# MHR15-GLV_PWR.net
KiCad netlist of a schematic drawn in EAGLE
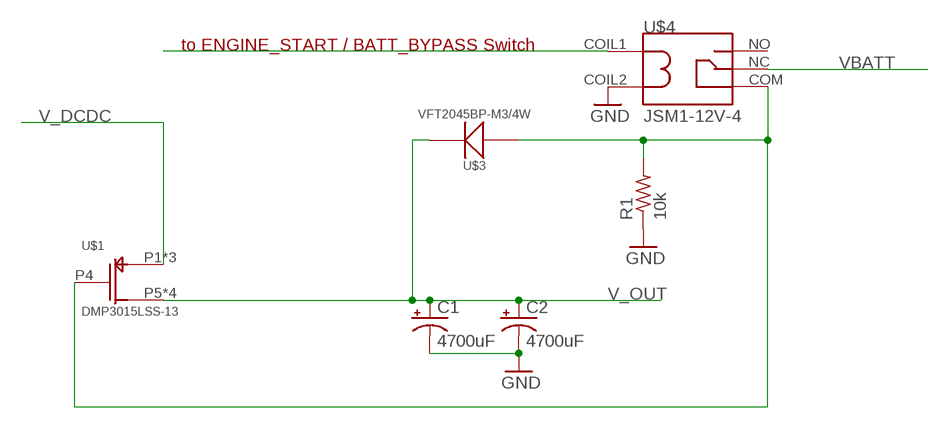
[diagram p0: schematic, sheet 1]

(export (version "E")
  (design (tool "Eeschema 10.0.6"))
  (components
    (comp (ref "C1")
      (value "4700uF")
      (footprint "eagle-import:CPOL-RADIAL-1000UF-63V")
      (libsource (lib "eagle-import") (part "CAP_POLPTH3"))
    )
    (comp (ref "C2")
      (value "4700uF")
      (footprint "eagle-import:CPOL-RADIAL-1000UF-63V")
      (libsource (lib "eagle-import") (part "CAP_POLPTH3"))
    )
    (comp (ref "R1")
      (value "10k")
      (footprint "eagle-import:R0603")
      (libsource (lib "eagle-import") (part "R-US_R0603"))
    )
    (comp (ref "U$1")
      (value "DMP3015LSS-13")
      (footprint "eagle-import:8-SOP")
      (fields (field (name "MANUFACTURER") "Diodes Incorporated"))
      (libsource (lib "eagle-import") (part "DMP3015LSS-13"))
    )
    (comp (ref "U$3")
      (value "VFT2045BP-M3/4W")
      (footprint "eagle-import:VFT2045BP-M3_4W")
      (fields (field (name "MANUFACTURER") "Vishay Semiconductor Diodes Division"))
      (libsource (lib "eagle-import") (part "VFT2045BP-M3/4W"))
    )
    (comp (ref "U$4")
      (value "JSM1-12V-4")
      (footprint "eagle-import:JSM1-12V-4")
      (fields (field (name "MANUFACTURER") "Panasonic Electric Works"))
      (libsource (lib "eagle-import") (part "JSM1-12V-4"))
    )
  )
  (nets
    (net (code "1") (name "/VBATT") (class "Default")
      (node (ref "U$4") (pin "NC") (pinfunction "NC_NC") (pintype "bidirectional"))
    )
    (net (code "2") (name "/V_DCDC") (class "Default")
      (node (ref "U$1") (pin "P1") (pinfunction "S_P1") (pintype "bidirectional"))
      (node (ref "U$1") (pin "P2") (pinfunction "S_P2") (pintype "bidirectional"))
      (node (ref "U$1") (pin "P3") (pinfunction "S_P3") (pintype "bidirectional"))
    )
    (net (code "3") (name "/V_OUT") (class "Default")
      (node (ref "C1") (pin "1") (pinfunction "+_1") (pintype "passive"))
      (node (ref "C2") (pin "1") (pinfunction "+_1") (pintype "passive"))
      (node (ref "U$1") (pin "P5") (pinfunction "D_P5") (pintype "bidirectional"))
      (node (ref "U$1") (pin "P6") (pinfunction "D_P6") (pintype "bidirectional"))
      (node (ref "U$1") (pin "P7") (pinfunction "D_P7") (pintype "bidirectional"))
      (node (ref "U$1") (pin "P8") (pinfunction "D_P8") (pintype "bidirectional"))
      (node (ref "U$3") (pin "P2") (pinfunction "P2_P2") (pintype "bidirectional"))
    )
    (net (code "4") (name "GND") (class "Default")
      (node (ref "C1") (pin "2") (pinfunction "-_2") (pintype "passive"))
      (node (ref "C2") (pin "2") (pinfunction "-_2") (pintype "passive"))
      (node (ref "R1") (pin "1") (pinfunction "1_1") (pintype "passive"))
      (node (ref "U$4") (pin "COIL2") (pinfunction "COIL2_COIL2") (pintype "bidirectional"))
    )
    (net (code "5") (name "Net-(U$1-G)") (class "Default")
      (node (ref "R1") (pin "2") (pinfunction "2_2") (pintype "passive"))
      (node (ref "U$1") (pin "P4") (pinfunction "G_P4") (pintype "bidirectional"))
      (node (ref "U$3") (pin "P1") (pinfunction "P1_P1") (pintype "bidirectional"))
      (node (ref "U$4") (pin "COM") (pinfunction "COM_COM") (pintype "bidirectional"))
    )
    (net (code "6") (name "unconnected-(U$4-PadCOIL1)") (class "Default")
      (node (ref "U$4") (pin "COIL1") (pinfunction "COIL1_COIL1") (pintype "bidirectional"))
    )
    (net (code "7") (name "unconnected-(U$4-PadNO)") (class "Default")
      (node (ref "U$4") (pin "NO") (pinfunction "NO_NO") (pintype "bidirectional"))
    )
  )
)
